# POWER_CON.net
KiCad netlist of a schematic drawn in Altium Designer
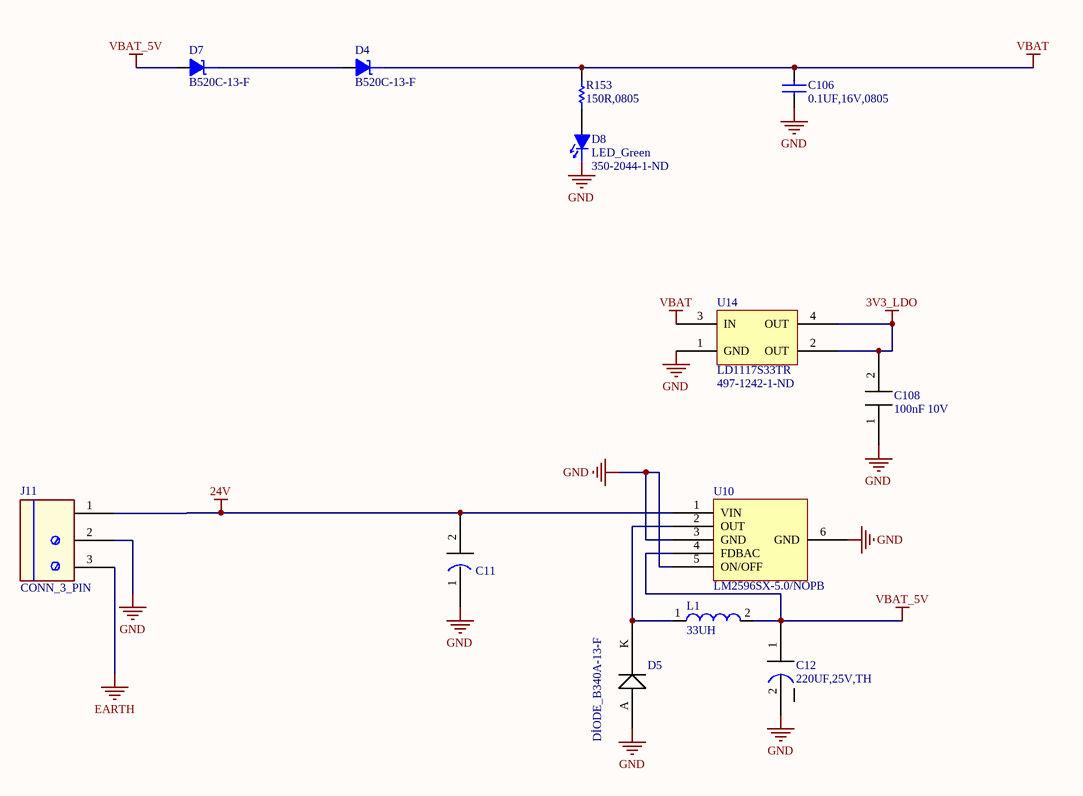
[diagram p0: POWER_CON.SchDoc]

(export (version "E")
  (design (tool "Eeschema 10.0.6"))
  (components
    (comp (ref "C11")
      (value "EKZE500ELL681MK30S")
      (footprint "HEADER,2PİN")
      (description "Aluminium Electrolytic Capacitors - Leaded 50volts 680uF 12.5X30")
      (fields (field (name "MANUFACTURER") "United Chemi-Con") (field (name "TOLERANCE") "20 %"))
      (libsource (lib "CPU_STM") (part "EKZE500ELL681MK30S"))
    )
    (comp (ref "C12")
      (value "220UF,25V,TH")
      (footprint "TH")
      (fields
        (field (name "MANUFACTURER") "Panasonic")
        (field (name "MANUFACTURER PART NUMBER") "EEU-FC1E221B")
        (field (name "TOLERANCE") "20 %")
      )
      (libsource (lib "CPU_STM") (part "220UF,25V,TH"))
    )
    (comp (ref "C106")
      (value "0.1UF,16V,0805")
      (footprint "0805")
      (description "AVX - 0805YC104KAT2A - CAP, MLCC, X7R, 100NF, 16V, 0805")
      (fields (field (name "MANUFACTURER") "AVX") (field (name "MANUFACTURER PART NUMBER") "0805YC104KAT2A"))
      (libsource (lib "LINUX") (part "0.1UF,16V,0805"))
    )
    (comp (ref "C108")
      (value "100nF 10V")
      (footprint "0805")
      (description "AVX - 08055C104JAT2A - CAP, MLCC, X7R, 100NF, 50V, 0805")
      (fields (field (name "MANUFACTURER") "AVX") (field (name "MANUFACTURER PART NUMBER") "08055C104JAT2A"))
      (libsource (lib "LINUX") (part "100nF 10V 8055C104JAT2A"))
    )
    (comp (ref "D4")
      (value "B520C-13-F")
      (footprint "B520C-13-F")
      (description "Diode Power Rectifier 5A Schottky")
      (fields (field (name "MFR") "Diodes Inc") (field (name "TIINTPARTNUMBER") "1E0012"))
      (libsource (lib "LINUX") (part "Diode_5ARect"))
    )
    (comp (ref "D5")
      (value "DİODE_B340A-13-F")
      (footprint "Diode")
      (description "MULTICOMP - B340A-13-F - DIODE, RECTIFIER, 3A, 40V, DO-214AC")
      (fields
        (field (name "MANUFACTURER") "MULTICOMP")
        (field (name "MANUFACTURER PART NUMBER") "B340A-13-F")
      )
      (libsource (lib "CPU_STM") (part "DİODE_B340A-13-F"))
    )
    (comp (ref "D7")
      (value "B520C-13-F")
      (footprint "B520C-13-F")
      (description "Diode Power Rectifier 5A Schottky")
      (fields (field (name "MFR") "Diodes Inc") (field (name "TIINTPARTNUMBER") "1E0012"))
      (libsource (lib "LINUX") (part "Diode_5ARect"))
    )
    (comp (ref "D8")
      (value "LED_Green")
      (footprint "LED_0805")
      (description "LED Green SMD 20mA 2V 0805")
      (fields
        (field (name "TIINTPARTNUMBER") "1F0008")
        (field (name "MFR") "Dialight")
        (field (name "SUPPLIER PART NUMBER 1") "350-2044-1-ND")
      )
      (libsource (lib "LINUX") (part "LED_Green"))
    )
    (comp (ref "J11")
      (value "CONN_3_PIN")
      (footprint "CON_3")
      (libsource (lib "CPU_STM") (part "CONN_3_PIN"))
    )
    (comp (ref "L1")
      (value "33UH")
      (footprint "indkrt_2")
      (description "Fixed Inductors 33uH 20% SMD 1260")
      (fields (field (name "MANUFACTURER") "Bourns") (field (name "MANUFACTURER PART NUMBER") "SRR1260-330M"))
      (libsource (lib "CPU_STM") (part "SRR1260-330M"))
    )
    (comp (ref "R153")
      (value "150R,0805")
      (footprint "0805")
      (description "TE CONNECTIVITY / NEOHM - CPF0805B150RE1 - RESISTOR, 0805, 150R")
      (fields
        (field (name "MANUFACTURER") "TE CONNECTIVITY / NEOHM")
        (field (name "MANUFACTURER PART NUMBER") "CPF0805B150RE1")
      )
      (libsource (lib "LINUX") (part "150R,0805"))
    )
    (comp (ref "U10")
      (value "LM2596SX-5.0/NOPB")
      (footprint "TO-263-5")
      (description "Voltage Regulators - Switching Regulators 150 KHZ 3A STEP-DOWN VLTG REG")
      (fields (field (name "MANUFACTURER") "Texas Instruments"))
      (libsource (lib "CPU_STM") (part "LM2596SX-5.0/NOPB"))
    )
    (comp (ref "U14")
      (value "LD1117S33TR")
      (footprint "SOT-223_L")
      (description "STMICROELECTRONICS - LD1117S33TR - IC, LDO VOLT REG, 3.3V, 0.8A, SOT-223-3")
      (fields
        (field (name "MANUFACTURER") "STMICROELECTRONICS")
        (field (name "SUPPLIER PART NUMBER 1") "497-1242-1-ND")
      )
      (libsource (lib "LINUX") (part "LD1117S33TR"))
    )
  )
  (nets
    (net (code "1") (name "3V3_LDO") (class "Default")
      (node (ref "C108") (pin "2") (pinfunction "15_2") (pintype "passive"))
      (node (ref "U14") (pin "2") (pinfunction "OUT_2") (pintype "passive"))
      (node (ref "U14") (pin "4") (pinfunction "OUT_4") (pintype "passive"))
    )
    (net (code "2") (name "24V") (class "Default")
      (node (ref "C11") (pin "2") (pinfunction "2_2") (pintype "passive"))
      (node (ref "J11") (pin "1") (pinfunction "1_1") (pintype "passive"))
      (node (ref "U10") (pin "1") (pinfunction "VIN_1") (pintype "passive"))
    )
    (net (code "3") (name "EARTH") (class "Default")
      (node (ref "J11") (pin "3") (pinfunction "3_3") (pintype "passive"))
    )
    (net (code "4") (name "GND") (class "Default")
      (node (ref "C106") (pin "1") (pinfunction "1_1") (pintype "passive"))
      (node (ref "C108") (pin "1") (pinfunction "14_1") (pintype "passive"))
      (node (ref "C11") (pin "1") (pinfunction "1_1") (pintype "passive"))
      (node (ref "C12") (pin "2") (pinfunction "2_2") (pintype "passive"))
      (node (ref "D5") (pin "A") (pinfunction "A_A") (pintype "passive"))
      (node (ref "D8") (pin "1") (pinfunction "Cathode_1") (pintype "passive"))
      (node (ref "J11") (pin "2") (pinfunction "2_2") (pintype "passive"))
      (node (ref "U10") (pin "3") (pinfunction "GND_3") (pintype "passive"))
      (node (ref "U10") (pin "5") (pinfunction "ON/OFF_5") (pintype "passive"))
      (node (ref "U10") (pin "6") (pinfunction "GND_6") (pintype "passive"))
      (node (ref "U14") (pin "1") (pinfunction "GND_1") (pintype "passive"))
    )
    (net (code "5") (name "Net-(D4-ANODE)") (class "Default")
      (node (ref "D4") (pin "2") (pinfunction "ANODE_2") (pintype "passive"))
      (node (ref "D7") (pin "1") (pinfunction "CATHODE_1") (pintype "passive"))
    )
    (net (code "6") (name "Net-(D8-Anode)") (class "Default")
      (node (ref "D8") (pin "2") (pinfunction "Anode_2") (pintype "passive"))
      (node (ref "R153") (pin "1") (pinfunction "1_1") (pintype "passive"))
    )
    (net (code "7") (name "Net-(U10-OUT)") (class "Default")
      (node (ref "D5") (pin "K") (pinfunction "K_K") (pintype "passive"))
      (node (ref "L1") (pin "1") (pinfunction "1_1") (pintype "passive"))
      (node (ref "U10") (pin "2") (pinfunction "OUT_2") (pintype "passive"))
    )
    (net (code "8") (name "VBAT") (class "Default")
      (node (ref "C106") (pin "2") (pinfunction "2_2") (pintype "passive"))
      (node (ref "D4") (pin "1") (pinfunction "CATHODE_1") (pintype "passive"))
      (node (ref "R153") (pin "2") (pinfunction "2_2") (pintype "passive"))
      (node (ref "U14") (pin "3") (pinfunction "IN_3") (pintype "passive"))
    )
    (net (code "9") (name "VBAT_5V") (class "Default")
      (node (ref "C12") (pin "1") (pinfunction "1_1") (pintype "passive"))
      (node (ref "D7") (pin "2") (pinfunction "ANODE_2") (pintype "passive"))
      (node (ref "L1") (pin "2") (pinfunction "2_2") (pintype "passive"))
      (node (ref "U10") (pin "4") (pinfunction "FDBAC_4") (pintype "passive"))
    )
  )
)
